# latdr32.net
KiCad netlist of a schematic drawn in EAGLE
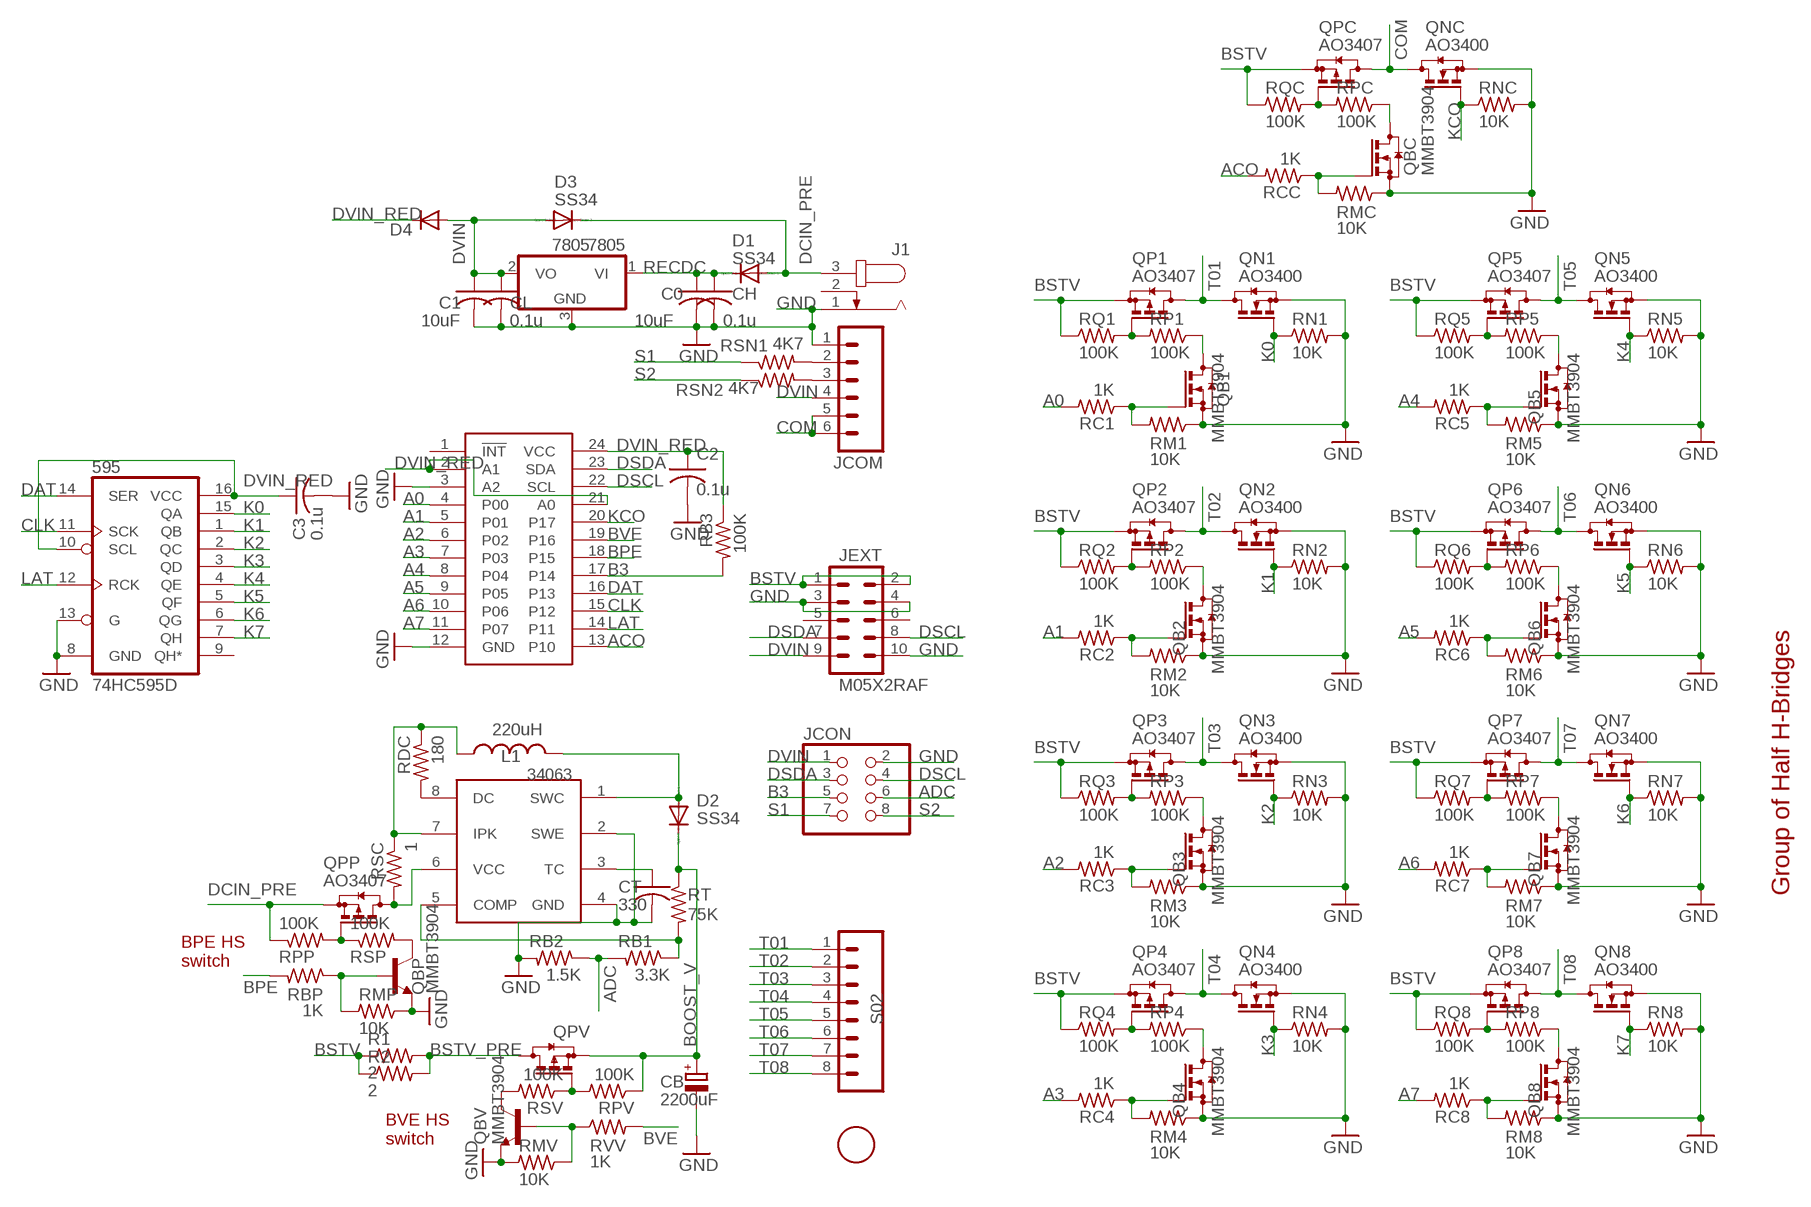
[diagram p0: schematic, sheet 1]

(export (version "E")
  (design (tool "Eeschema 10.0.6"))
  (components
    (comp (ref "1F")
      (value "FIDUCIAL")
      (footprint "eagle-import:FIDUCIAL_1MM")
      (libsource (lib "eagle-import") (part "FIDUCIAL"))
    )
    (comp (ref "595")
      (value "74HC595D")
      (footprint "eagle-import:SO16")
      (libsource (lib "eagle-import") (part "74595DLS"))
    )
    (comp (ref "7805")
      (value "7805")
      (footprint "eagle-import:TO252")
      (libsource (lib "eagle-import") (part "78DT05"))
    )
    (comp (ref "34063")
      (value "MC34063")
      (footprint "eagle-import:SO08")
      (libsource (lib "eagle-import") (part "MC33063/MC34063D"))
    )
    (comp (ref "C0")
      (value "10uF")
      (footprint "eagle-import:C0805K")
      (libsource (lib "eagle-import") (part "C-USC0805K"))
    )
    (comp (ref "C1")
      (value "10uF")
      (footprint "eagle-import:C0805K")
      (libsource (lib "eagle-import") (part "C-USC0805K"))
    )
    (comp (ref "C2")
      (value "0.1u")
      (footprint "eagle-import:C0603")
      (libsource (lib "eagle-import") (part "C-USC0603"))
    )
    (comp (ref "C3")
      (value "0.1u")
      (footprint "eagle-import:C0603")
      (libsource (lib "eagle-import") (part "C-USC0603"))
    )
    (comp (ref "CB")
      (value "2200uF")
      (footprint "eagle-import:E7,5-16")
      (libsource (lib "eagle-import") (part "CPOL-EUE7.5-16"))
    )
    (comp (ref "CH")
      (value "0.1u")
      (footprint "eagle-import:C0603")
      (libsource (lib "eagle-import") (part "C-USC0603"))
    )
    (comp (ref "CL")
      (value "0.1u")
      (footprint "eagle-import:C0603")
      (libsource (lib "eagle-import") (part "C-USC0603"))
    )
    (comp (ref "CT")
      (value "330")
      (footprint "eagle-import:C0603K")
      (libsource (lib "eagle-import") (part "C-USC0603K"))
    )
    (comp (ref "D1")
      (value "SS34")
      (footprint "eagle-import:SMB")
      (libsource (lib "eagle-import") (part "DIODE-SMB"))
    )
    (comp (ref "D2")
      (value "SS34")
      (footprint "eagle-import:SMB")
      (libsource (lib "eagle-import") (part "DIODE-SMB"))
    )
    (comp (ref "D3")
      (value "SS34")
      (footprint "eagle-import:SMB")
      (libsource (lib "eagle-import") (part "DIODE-SMB"))
    )
    (comp (ref "D4")
      (value "DIODESMA")
      (footprint "eagle-import:SMA-DIODE")
      (libsource (lib "eagle-import") (part "DIODESMA"))
    )
    (comp (ref "J1")
      (value "JACK-PLUG0")
      (footprint "eagle-import:SPC4077")
      (libsource (lib "eagle-import") (part "JACK-PLUG0"))
    )
    (comp (ref "JCOM")
      (value "M065MM")
      (footprint "eagle-import:SCREWTERMINAL-5MM-6")
      (libsource (lib "eagle-import") (part "M065MM"))
    )
    (comp (ref "JCON")
      (value "PINHD-2X4")
      (footprint "eagle-import:2X04")
      (libsource (lib "eagle-import") (part "PINHD-2X4"))
    )
    (comp (ref "JEXT")
      (value "M05X2RAF")
      (footprint "eagle-import:2X5-RAF")
      (libsource (lib "eagle-import") (part "M05X2RAF"))
    )
    (comp (ref "L1")
      (value "220uH")
      (footprint "eagle-import:CR54")
      (libsource (lib "eagle-import") (part "INDUCTORCR54"))
    )
    (comp (ref "PCA9555")
      (value "PCA9555")
      (footprint "eagle-import:TSSOP24")
      (libsource (lib "eagle-import") (part "PCF8575TSSOP24"))
    )
    (comp (ref "QB1")
      (value "MMBT3904")
      (footprint "eagle-import:SOT23")
      (libsource (lib "eagle-import") (part "BSS123"))
    )
    (comp (ref "QB2")
      (value "MMBT3904")
      (footprint "eagle-import:SOT23")
      (libsource (lib "eagle-import") (part "BSS123"))
    )
    (comp (ref "QB3")
      (value "MMBT3904")
      (footprint "eagle-import:SOT23")
      (libsource (lib "eagle-import") (part "BSS123"))
    )
    (comp (ref "QB4")
      (value "MMBT3904")
      (footprint "eagle-import:SOT23")
      (libsource (lib "eagle-import") (part "BSS123"))
    )
    (comp (ref "QB5")
      (value "MMBT3904")
      (footprint "eagle-import:SOT23")
      (libsource (lib "eagle-import") (part "BSS123"))
    )
    (comp (ref "QB6")
      (value "MMBT3904")
      (footprint "eagle-import:SOT23")
      (libsource (lib "eagle-import") (part "BSS123"))
    )
    (comp (ref "QB7")
      (value "MMBT3904")
      (footprint "eagle-import:SOT23")
      (libsource (lib "eagle-import") (part "BSS123"))
    )
    (comp (ref "QB8")
      (value "MMBT3904")
      (footprint "eagle-import:SOT23")
      (libsource (lib "eagle-import") (part "BSS123"))
    )
    (comp (ref "QBC")
      (value "MMBT3904")
      (footprint "eagle-import:SOT23")
      (libsource (lib "eagle-import") (part "BSS123"))
    )
    (comp (ref "QBP")
      (value "MMBT3904")
      (footprint "eagle-import:SOT23-3")
      (libsource (lib "eagle-import") (part "TRANSISTOR_NPNSOT23-3"))
    )
    (comp (ref "QBV")
      (value "MMBT3904")
      (footprint "eagle-import:SOT23-3")
      (libsource (lib "eagle-import") (part "TRANSISTOR_NPNSOT23-3"))
    )
    (comp (ref "QN1")
      (value "AO3400")
      (footprint "eagle-import:SOT23")
      (libsource (lib "eagle-import") (part "BSS123"))
    )
    (comp (ref "QN2")
      (value "AO3400")
      (footprint "eagle-import:SOT23")
      (libsource (lib "eagle-import") (part "BSS123"))
    )
    (comp (ref "QN3")
      (value "AO3400")
      (footprint "eagle-import:SOT23")
      (libsource (lib "eagle-import") (part "BSS123"))
    )
    (comp (ref "QN4")
      (value "AO3400")
      (footprint "eagle-import:SOT23")
      (libsource (lib "eagle-import") (part "BSS123"))
    )
    (comp (ref "QN5")
      (value "AO3400")
      (footprint "eagle-import:SOT23")
      (libsource (lib "eagle-import") (part "BSS123"))
    )
    (comp (ref "QN6")
      (value "AO3400")
      (footprint "eagle-import:SOT23")
      (libsource (lib "eagle-import") (part "BSS123"))
    )
    (comp (ref "QN7")
      (value "AO3400")
      (footprint "eagle-import:SOT23")
      (libsource (lib "eagle-import") (part "BSS123"))
    )
    (comp (ref "QN8")
      (value "AO3400")
      (footprint "eagle-import:SOT23")
      (libsource (lib "eagle-import") (part "BSS123"))
    )
    (comp (ref "QNC")
      (value "AO3400")
      (footprint "eagle-import:SOT23")
      (libsource (lib "eagle-import") (part "BSS123"))
    )
    (comp (ref "QP1")
      (value "AO3407")
      (footprint "eagle-import:SOT23")
      (libsource (lib "eagle-import") (part "BSS84"))
    )
    (comp (ref "QP2")
      (value "AO3407")
      (footprint "eagle-import:SOT23")
      (libsource (lib "eagle-import") (part "BSS84"))
    )
    (comp (ref "QP3")
      (value "AO3407")
      (footprint "eagle-import:SOT23")
      (libsource (lib "eagle-import") (part "BSS84"))
    )
    (comp (ref "QP4")
      (value "AO3407")
      (footprint "eagle-import:SOT23")
      (libsource (lib "eagle-import") (part "BSS84"))
    )
    (comp (ref "QP5")
      (value "AO3407")
      (footprint "eagle-import:SOT23")
      (libsource (lib "eagle-import") (part "BSS84"))
    )
    (comp (ref "QP6")
      (value "AO3407")
      (footprint "eagle-import:SOT23")
      (libsource (lib "eagle-import") (part "BSS84"))
    )
    (comp (ref "QP7")
      (value "AO3407")
      (footprint "eagle-import:SOT23")
      (libsource (lib "eagle-import") (part "BSS84"))
    )
    (comp (ref "QP8")
      (value "AO3407")
      (footprint "eagle-import:SOT23")
      (libsource (lib "eagle-import") (part "BSS84"))
    )
    (comp (ref "QPC")
      (value "AO3407")
      (footprint "eagle-import:SOT23")
      (libsource (lib "eagle-import") (part "BSS84"))
    )
    (comp (ref "QPP")
      (value "AO3407")
      (footprint "eagle-import:SOT23")
      (libsource (lib "eagle-import") (part "BSS84"))
    )
    (comp (ref "QPV")
      (value "AO3407")
      (footprint "eagle-import:SOT23")
      (libsource (lib "eagle-import") (part "BSS84"))
    )
    (comp (ref "R1")
      (value "2")
      (footprint "eagle-import:R2512")
      (libsource (lib "eagle-import") (part "R-US_R2512"))
    )
    (comp (ref "R2")
      (value "2")
      (footprint "eagle-import:R2512")
      (libsource (lib "eagle-import") (part "R-US_R2512"))
    )
    (comp (ref "RB1")
      (value "3.3K")
      (footprint "eagle-import:R0603")
      (libsource (lib "eagle-import") (part "adafruitGood_R-US_R0603"))
    )
    (comp (ref "RB2")
      (value "1.5K")
      (footprint "eagle-import:R0603")
      (libsource (lib "eagle-import") (part "adafruitGood_R-US_R0603"))
    )
    (comp (ref "RB3")
      (value "100K")
      (footprint "eagle-import:R0603")
      (libsource (lib "eagle-import") (part "adafruitGood_R-US_R0603"))
    )
    (comp (ref "RBP")
      (value "1K")
      (footprint "eagle-import:R0603")
      (libsource (lib "eagle-import") (part "adafruitGood_R-US_R0603"))
    )
    (comp (ref "RC1")
      (value "1K")
      (footprint "eagle-import:R0603")
      (libsource (lib "eagle-import") (part "adafruitGood_R-US_R0603"))
    )
    (comp (ref "RC2")
      (value "1K")
      (footprint "eagle-import:R0603")
      (libsource (lib "eagle-import") (part "adafruitGood_R-US_R0603"))
    )
    (comp (ref "RC3")
      (value "1K")
      (footprint "eagle-import:R0603")
      (libsource (lib "eagle-import") (part "adafruitGood_R-US_R0603"))
    )
    (comp (ref "RC4")
      (value "1K")
      (footprint "eagle-import:R0603")
      (libsource (lib "eagle-import") (part "adafruitGood_R-US_R0603"))
    )
    (comp (ref "RC5")
      (value "1K")
      (footprint "eagle-import:R0603")
      (libsource (lib "eagle-import") (part "adafruitGood_R-US_R0603"))
    )
    (comp (ref "RC6")
      (value "1K")
      (footprint "eagle-import:R0603")
      (libsource (lib "eagle-import") (part "adafruitGood_R-US_R0603"))
    )
    (comp (ref "RC7")
      (value "1K")
      (footprint "eagle-import:R0603")
      (libsource (lib "eagle-import") (part "adafruitGood_R-US_R0603"))
    )
    (comp (ref "RC8")
      (value "1K")
      (footprint "eagle-import:R0603")
      (libsource (lib "eagle-import") (part "adafruitGood_R-US_R0603"))
    )
    (comp (ref "RCC")
      (value "1K")
      (footprint "eagle-import:R0603")
      (libsource (lib "eagle-import") (part "adafruitGood_R-US_R0603"))
    )
    (comp (ref "RDC")
      (value "180")
      (footprint "eagle-import:R0603")
      (libsource (lib "eagle-import") (part "adafruitGood_R-US_R0603"))
    )
    (comp (ref "RM1")
      (value "10K")
      (footprint "eagle-import:R0603")
      (libsource (lib "eagle-import") (part "adafruitGood_R-US_R0603"))
    )
    (comp (ref "RM2")
      (value "10K")
      (footprint "eagle-import:R0603")
      (libsource (lib "eagle-import") (part "adafruitGood_R-US_R0603"))
    )
    (comp (ref "RM3")
      (value "10K")
      (footprint "eagle-import:R0603")
      (libsource (lib "eagle-import") (part "adafruitGood_R-US_R0603"))
    )
    (comp (ref "RM4")
      (value "10K")
      (footprint "eagle-import:R0603")
      (libsource (lib "eagle-import") (part "adafruitGood_R-US_R0603"))
    )
    (comp (ref "RM5")
      (value "10K")
      (footprint "eagle-import:R0603")
      (libsource (lib "eagle-import") (part "adafruitGood_R-US_R0603"))
    )
    (comp (ref "RM6")
      (value "10K")
      (footprint "eagle-import:R0603")
      (libsource (lib "eagle-import") (part "adafruitGood_R-US_R0603"))
    )
    (comp (ref "RM7")
      (value "10K")
      (footprint "eagle-import:R0603")
      (libsource (lib "eagle-import") (part "adafruitGood_R-US_R0603"))
    )
    (comp (ref "RM8")
      (value "10K")
      (footprint "eagle-import:R0603")
      (libsource (lib "eagle-import") (part "adafruitGood_R-US_R0603"))
    )
    (comp (ref "RMC")
      (value "10K")
      (footprint "eagle-import:R0603")
      (libsource (lib "eagle-import") (part "adafruitGood_R-US_R0603"))
    )
    (comp (ref "RMP")
      (value "10K")
      (footprint "eagle-import:R0603")
      (libsource (lib "eagle-import") (part "adafruitGood_R-US_R0603"))
    )
    (comp (ref "RMV")
      (value "10K")
      (footprint "eagle-import:R0603")
      (libsource (lib "eagle-import") (part "adafruitGood_R-US_R0603"))
    )
    (comp (ref "RN1")
      (value "10K")
      (footprint "eagle-import:R0603")
      (libsource (lib "eagle-import") (part "adafruitGood_R-US_R0603"))
    )
    (comp (ref "RN2")
      (value "10K")
      (footprint "eagle-import:R0603")
      (libsource (lib "eagle-import") (part "adafruitGood_R-US_R0603"))
    )
    (comp (ref "RN3")
      (value "10K")
      (footprint "eagle-import:R0603")
      (libsource (lib "eagle-import") (part "adafruitGood_R-US_R0603"))
    )
    (comp (ref "RN4")
      (value "10K")
      (footprint "eagle-import:R0603")
      (libsource (lib "eagle-import") (part "adafruitGood_R-US_R0603"))
    )
    (comp (ref "RN5")
      (value "10K")
      (footprint "eagle-import:R0603")
      (libsource (lib "eagle-import") (part "adafruitGood_R-US_R0603"))
    )
    (comp (ref "RN6")
      (value "10K")
      (footprint "eagle-import:R0603")
      (libsource (lib "eagle-import") (part "adafruitGood_R-US_R0603"))
    )
    (comp (ref "RN7")
      (value "10K")
      (footprint "eagle-import:R0603")
      (libsource (lib "eagle-import") (part "adafruitGood_R-US_R0603"))
    )
    (comp (ref "RN8")
      (value "10K")
      (footprint "eagle-import:R0603")
      (libsource (lib "eagle-import") (part "adafruitGood_R-US_R0603"))
    )
    (comp (ref "RNC")
      (value "10K")
      (footprint "eagle-import:R0603")
      (libsource (lib "eagle-import") (part "adafruitGood_R-US_R0603"))
    )
    (comp (ref "RP1")
      (value "100K")
      (footprint "eagle-import:R0603")
      (libsource (lib "eagle-import") (part "adafruitGood_R-US_R0603"))
    )
    (comp (ref "RP2")
      (value "100K")
      (footprint "eagle-import:R0603")
      (libsource (lib "eagle-import") (part "adafruitGood_R-US_R0603"))
    )
    (comp (ref "RP3")
      (value "100K")
      (footprint "eagle-import:R0603")
      (libsource (lib "eagle-import") (part "adafruitGood_R-US_R0603"))
    )
    (comp (ref "RP4")
      (value "100K")
      (footprint "eagle-import:R0603")
      (libsource (lib "eagle-import") (part "adafruitGood_R-US_R0603"))
    )
    (comp (ref "RP5")
      (value "100K")
      (footprint "eagle-import:R0603")
      (libsource (lib "eagle-import") (part "adafruitGood_R-US_R0603"))
    )
    (comp (ref "RP6")
      (value "100K")
      (footprint "eagle-import:R0603")
      (libsource (lib "eagle-import") (part "adafruitGood_R-US_R0603"))
    )
    (comp (ref "RP7")
      (value "100K")
      (footprint "eagle-import:R0603")
      (libsource (lib "eagle-import") (part "adafruitGood_R-US_R0603"))
    )
    (comp (ref "RP8")
      (value "100K")
      (footprint "eagle-import:R0603")
      (libsource (lib "eagle-import") (part "adafruitGood_R-US_R0603"))
    )
    (comp (ref "RPC")
      (value "100K")
      (footprint "eagle-import:R0603")
      (libsource (lib "eagle-import") (part "adafruitGood_R-US_R0603"))
    )
    (comp (ref "RPP")
      (value "100K")
      (footprint "eagle-import:R0603")
      (libsource (lib "eagle-import") (part "adafruitGood_R-US_R0603"))
    )
    (comp (ref "RPV")
      (value "100K")
      (footprint "eagle-import:R0603")
      (libsource (lib "eagle-import") (part "adafruitGood_R-US_R0603"))
    )
    (comp (ref "RQ1")
      (value "100K")
      (footprint "eagle-import:R0603")
      (libsource (lib "eagle-import") (part "adafruitGood_R-US_R0603"))
    )
    (comp (ref "RQ2")
      (value "100K")
      (footprint "eagle-import:R0603")
      (libsource (lib "eagle-import") (part "adafruitGood_R-US_R0603"))
    )
    (comp (ref "RQ3")
      (value "100K")
      (footprint "eagle-import:R0603")
      (libsource (lib "eagle-import") (part "adafruitGood_R-US_R0603"))
    )
    (comp (ref "RQ4")
      (value "100K")
      (footprint "eagle-import:R0603")
      (libsource (lib "eagle-import") (part "adafruitGood_R-US_R0603"))
    )
    (comp (ref "RQ5")
      (value "100K")
      (footprint "eagle-import:R0603")
      (libsource (lib "eagle-import") (part "adafruitGood_R-US_R0603"))
    )
    (comp (ref "RQ6")
      (value "100K")
      (footprint "eagle-import:R0603")
      (libsource (lib "eagle-import") (part "adafruitGood_R-US_R0603"))
    )
    (comp (ref "RQ7")
      (value "100K")
      (footprint "eagle-import:R0603")
      (libsource (lib "eagle-import") (part "adafruitGood_R-US_R0603"))
    )
    (comp (ref "RQ8")
      (value "100K")
      (footprint "eagle-import:R0603")
      (libsource (lib "eagle-import") (part "adafruitGood_R-US_R0603"))
    )
    (comp (ref "RQC")
      (value "100K")
      (footprint "eagle-import:R0603")
      (libsource (lib "eagle-import") (part "adafruitGood_R-US_R0603"))
    )
    (comp (ref "RSC")
      (value "1")
      (footprint "eagle-import:R0603")
      (libsource (lib "eagle-import") (part "adafruitGood_R-US_R0603"))
    )
    (comp (ref "RSN1")
      (value "4K7")
      (footprint "eagle-import:R0603")
      (libsource (lib "eagle-import") (part "R-US_R0603"))
    )
    (comp (ref "RSN2")
      (value "4K7")
      (footprint "eagle-import:R0603")
      (libsource (lib "eagle-import") (part "R-US_R0603"))
    )
    (comp (ref "RSP")
      (value "100K")
      (footprint "eagle-import:R0603")
      (libsource (lib "eagle-import") (part "adafruitGood_R-US_R0603"))
    )
    (comp (ref "RSV")
      (value "100K")
      (footprint "eagle-import:R0603")
      (libsource (lib "eagle-import") (part "adafruitGood_R-US_R0603"))
    )
    (comp (ref "RT")
      (value "75K")
      (footprint "eagle-import:R0603")
      (libsource (lib "eagle-import") (part "adafruitGood_R-US_R0603"))
    )
    (comp (ref "RVV")
      (value "1K")
      (footprint "eagle-import:R0603")
      (libsource (lib "eagle-import") (part "adafruitGood_R-US_R0603"))
    )
    (comp (ref "S02")
      (value "M085MM-8")
      (footprint "eagle-import:SCREWTERMINAL-5MM-8")
      (libsource (lib "eagle-import") (part "M085MM-8"))
    )
  )
  (nets
    (net (code "1") (name "/A0") (class "Default")
      (node (ref "PCA9555") (pin "4") (pinfunction "P00_4") (pintype "bidirectional"))
      (node (ref "RC1") (pin "2") (pinfunction "2_2") (pintype "passive"))
    )
    (net (code "2") (name "/A1") (class "Default")
      (node (ref "PCA9555") (pin "5") (pinfunction "P01_5") (pintype "bidirectional"))
      (node (ref "RC2") (pin "2") (pinfunction "2_2") (pintype "passive"))
    )
    (net (code "3") (name "/A2") (class "Default")
      (node (ref "PCA9555") (pin "6") (pinfunction "P02_6") (pintype "bidirectional"))
      (node (ref "RC3") (pin "2") (pinfunction "2_2") (pintype "passive"))
    )
    (net (code "4") (name "/A3") (class "Default")
      (node (ref "PCA9555") (pin "7") (pinfunction "P03_7") (pintype "bidirectional"))
      (node (ref "RC4") (pin "2") (pinfunction "2_2") (pintype "passive"))
    )
    (net (code "5") (name "/A4") (class "Default")
      (node (ref "PCA9555") (pin "8") (pinfunction "P04_8") (pintype "bidirectional"))
      (node (ref "RC5") (pin "2") (pinfunction "2_2") (pintype "passive"))
    )
    (net (code "6") (name "/A5") (class "Default")
      (node (ref "PCA9555") (pin "9") (pinfunction "P05_9") (pintype "bidirectional"))
      (node (ref "RC6") (pin "2") (pinfunction "2_2") (pintype "passive"))
    )
    (net (code "7") (name "/A6") (class "Default")
      (node (ref "PCA9555") (pin "10") (pinfunction "P06_10") (pintype "bidirectional"))
      (node (ref "RC7") (pin "2") (pinfunction "2_2") (pintype "passive"))
    )
    (net (code "8") (name "/A7") (class "Default")
      (node (ref "PCA9555") (pin "11") (pinfunction "P07_11") (pintype "bidirectional"))
      (node (ref "RC8") (pin "2") (pinfunction "2_2") (pintype "passive"))
    )
    (net (code "9") (name "/ACO") (class "Default")
      (node (ref "PCA9555") (pin "13") (pinfunction "P10_13") (pintype "bidirectional"))
      (node (ref "RCC") (pin "2") (pinfunction "2_2") (pintype "passive"))
    )
    (net (code "10") (name "/ADC") (class "Default")
      (node (ref "JCON") (pin "6") (pinfunction "6_6") (pintype "passive"))
      (node (ref "RB1") (pin "2") (pinfunction "2_2") (pintype "passive"))
      (node (ref "RB2") (pin "1") (pinfunction "1_1") (pintype "passive"))
    )
    (net (code "11") (name "/B3") (class "Default")
      (node (ref "JCON") (pin "5") (pinfunction "5_5") (pintype "passive"))
      (node (ref "PCA9555") (pin "17") (pinfunction "P14_17") (pintype "bidirectional"))
      (node (ref "RB3") (pin "2") (pinfunction "2_2") (pintype "passive"))
    )
    (net (code "12") (name "/BOOST_V") (class "Default")
      (node (ref "CB") (pin "+") (pinfunction "+_+") (pintype "passive"))
      (node (ref "D2") (pin "C") (pinfunction "C_C") (pintype "passive"))
      (node (ref "QPV") (pin "2") (pinfunction "S_2") (pintype "passive"))
      (node (ref "RPV") (pin "1") (pinfunction "1_1") (pintype "passive"))
      (node (ref "RT") (pin "1") (pinfunction "1_1") (pintype "passive"))
    )
    (net (code "13") (name "/BPE") (class "Default")
      (node (ref "PCA9555") (pin "18") (pinfunction "P15_18") (pintype "bidirectional"))
      (node (ref "RBP") (pin "2") (pinfunction "2_2") (pintype "passive"))
    )
    (net (code "14") (name "/BSTV") (class "Default")
      (node (ref "JEXT") (pin "1") (pinfunction "1_1") (pintype "passive"))
      (node (ref "JEXT") (pin "2") (pinfunction "2_2") (pintype "passive"))
      (node (ref "QP1") (pin "2") (pinfunction "S_2") (pintype "passive"))
      (node (ref "QP2") (pin "2") (pinfunction "S_2") (pintype "passive"))
      (node (ref "QP3") (pin "2") (pinfunction "S_2") (pintype "passive"))
      (node (ref "QP4") (pin "2") (pinfunction "S_2") (pintype "passive"))
      (node (ref "QP5") (pin "2") (pinfunction "S_2") (pintype "passive"))
      (node (ref "QP6") (pin "2") (pinfunction "S_2") (pintype "passive"))
      (node (ref "QP7") (pin "2") (pinfunction "S_2") (pintype "passive"))
      (node (ref "QP8") (pin "2") (pinfunction "S_2") (pintype "passive"))
      (node (ref "QPC") (pin "2") (pinfunction "S_2") (pintype "passive"))
      (node (ref "R1") (pin "1") (pinfunction "1_1") (pintype "passive"))
      (node (ref "R2") (pin "1") (pinfunction "1_1") (pintype "passive"))
      (node (ref "RQ1") (pin "1") (pinfunction "1_1") (pintype "passive"))
      (node (ref "RQ2") (pin "1") (pinfunction "1_1") (pintype "passive"))
      (node (ref "RQ3") (pin "1") (pinfunction "1_1") (pintype "passive"))
      (node (ref "RQ4") (pin "1") (pinfunction "1_1") (pintype "passive"))
      (node (ref "RQ5") (pin "1") (pinfunction "1_1") (pintype "passive"))
      (node (ref "RQ6") (pin "1") (pinfunction "1_1") (pintype "passive"))
      (node (ref "RQ7") (pin "1") (pinfunction "1_1") (pintype "passive"))
      (node (ref "RQ8") (pin "1") (pinfunction "1_1") (pintype "passive"))
      (node (ref "RQC") (pin "1") (pinfunction "1_1") (pintype "passive"))
    )
    (net (code "15") (name "/BSTV_PRE") (class "Default")
      (node (ref "QPV") (pin "3") (pinfunction "D_3") (pintype "passive"))
      (node (ref "R1") (pin "2") (pinfunction "2_2") (pintype "passive"))
      (node (ref "R2") (pin "2") (pinfunction "2_2") (pintype "passive"))
    )
    (net (code "16") (name "/BVE") (class "Default")
      (node (ref "PCA9555") (pin "19") (pinfunction "P16_19") (pintype "bidirectional"))
      (node (ref "RVV") (pin "2") (pinfunction "2_2") (pintype "passive"))
    )
    (net (code "17") (name "/CLK") (class "Default")
      (node (ref "595") (pin "11") (pinfunction "SCK_11") (pintype "input"))
      (node (ref "PCA9555") (pin "15") (pinfunction "P12_15") (pintype "bidirectional"))
    )
    (net (code "18") (name "/COM") (class "Default")
      (node (ref "JCOM") (pin "5") (pinfunction "5_5") (pintype "passive"))
      (node (ref "JCOM") (pin "6") (pinfunction "6_6") (pintype "passive"))
      (node (ref "QNC") (pin "3") (pinfunction "D_3") (pintype "passive"))
      (node (ref "QPC") (pin "3") (pinfunction "D_3") (pintype "passive"))
    )
    (net (code "19") (name "/DAT") (class "Default")
      (node (ref "595") (pin "14") (pinfunction "SER_14") (pintype "input"))
      (node (ref "PCA9555") (pin "16") (pinfunction "P13_16") (pintype "bidirectional"))
    )
    (net (code "20") (name "/DCIN_PRE") (class "Default")
      (node (ref "D1") (pin "A") (pinfunction "A_A") (pintype "passive"))
      (node (ref "D3") (pin "C") (pinfunction "C_C") (pintype "passive"))
      (node (ref "J1") (pin "3") (pinfunction "3_3") (pintype "passive"))
      (node (ref "QPP") (pin "2") (pinfunction "S_2") (pintype "passive"))
      (node (ref "RPP") (pin "1") (pinfunction "1_1") (pintype "passive"))
    )
    (net (code "21") (name "/DSCL") (class "Default")
      (node (ref "JCON") (pin "4") (pinfunction "4_4") (pintype "passive"))
      (node (ref "JEXT") (pin "8") (pinfunction "8_8") (pintype "passive"))
      (node (ref "PCA9555") (pin "22") (pinfunction "SCL_22") (pintype "bidirectional"))
    )
    (net (code "22") (name "/DSDA") (class "Default")
      (node (ref "JCON") (pin "3") (pinfunction "3_3") (pintype "passive"))
      (node (ref "JEXT") (pin "7") (pinfunction "7_7") (pintype "passive"))
      (node (ref "PCA9555") (pin "23") (pinfunction "SDA_23") (pintype "bidirectional"))
    )
    (net (code "23") (name "/DVIN") (class "Default")
      (node (ref "7805") (pin "2") (pinfunction "VO_2") (pintype "passive"))
      (node (ref "C1") (pin "1") (pinfunction "1_1") (pintype "passive"))
      (node (ref "CL") (pin "1") (pinfunction "1_1") (pintype "passive"))
      (node (ref "D3") (pin "A") (pinfunction "A_A") (pintype "passive"))
      (node (ref "D4") (pin "A") (pinfunction "A_A") (pintype "passive"))
      (node (ref "JCOM") (pin "4") (pinfunction "4_4") (pintype "passive"))
      (node (ref "JCON") (pin "1") (pinfunction "1_1") (pintype "passive"))
      (node (ref "JEXT") (pin "9") (pinfunction "9_9") (pintype "passive"))
    )
    (net (code "24") (name "/DVIN_RED") (class "Default")
      (node (ref "595") (pin "10") (pinfunction "SCL_10") (pintype "input"))
      (node (ref "595") (pin "16") (pinfunction "VCC_16") (pintype "power_in"))
      (node (ref "C2") (pin "1") (pinfunction "1_1") (pintype "passive"))
      (node (ref "C3") (pin "1") (pinfunction "1_1") (pintype "passive"))
      (node (ref "D4") (pin "C") (pinfunction "C_C") (pintype "passive"))
      (node (ref "PCA9555") (pin "2") (pinfunction "A1_2") (pintype "bidirectional"))
      (node (ref "PCA9555") (pin "21") (pinfunction "A0_21") (pintype "bidirectional"))
      (node (ref "PCA9555") (pin "24") (pinfunction "VCC_24") (pintype "power_in"))
      (node (ref "RB3") (pin "1") (pinfunction "1_1") (pintype "passive"))
    )
    (net (code "25") (name "/K0") (class "Default")
      (node (ref "595") (pin "15") (pinfunction "QA_15") (pintype "tri_state"))
      (node (ref "QN1") (pin "1") (pinfunction "G_1") (pintype "passive"))
      (node (ref "RN1") (pin "1") (pinfunction "1_1") (pintype "passive"))
    )
    (net (code "26") (name "/K1") (class "Default")
      (node (ref "595") (pin "1") (pinfunction "QB_1") (pintype "tri_state"))
      (node (ref "QN2") (pin "1") (pinfunction "G_1") (pintype "passive"))
      (node (ref "RN2") (pin "1") (pinfunction "1_1") (pintype "passive"))
    )
    (net (code "27") (name "/K2") (class "Default")
      (node (ref "595") (pin "2") (pinfunction "QC_2") (pintype "tri_state"))
      (node (ref "QN3") (pin "1") (pinfunction "G_1") (pintype "passive"))
      (node (ref "RN3") (pin "1") (pinfunction "1_1") (pintype "passive"))
    )
    (net (code "28") (name "/K3") (class "Default")
      (node (ref "595") (pin "3") (pinfunction "QD_3") (pintype "tri_state"))
      (node (ref "QN4") (pin "1") (pinfunction "G_1") (pintype "passive"))
      (node (ref "RN4") (pin "1") (pinfunction "1_1") (pintype "passive"))
    )
    (net (code "29") (name "/K4") (class "Default")
      (node (ref "595") (pin "4") (pinfunction "QE_4") (pintype "tri_state"))
      (node (ref "QN5") (pin "1") (pinfunction "G_1") (pintype "passive"))
      (node (ref "RN5") (pin "1") (pinfunction "1_1") (pintype "passive"))
    )
    (net (code "30") (name "/K5") (class "Default")
      (node (ref "595") (pin "5") (pinfunction "QF_5") (pintype "tri_state"))
      (node (ref "QN6") (pin "1") (pinfunction "G_1") (pintype "passive"))
      (node (ref "RN6") (pin "1") (pinfunction "1_1") (pintype "passive"))
    )
    (net (code "31") (name "/K6") (class "Default")
      (node (ref "595") (pin "6") (pinfunction "QG_6") (pintype "tri_state"))
      (node (ref "QN7") (pin "1") (pinfunction "G_1") (pintype "passive"))
      (node (ref "RN7") (pin "1") (pinfunction "1_1") (pintype "passive"))
    )
    (net (code "32") (name "/K7") (class "Default")
      (node (ref "595") (pin "7") (pinfunction "QH_7") (pintype "tri_state"))
      (node (ref "QN8") (pin "1") (pinfunction "G_1") (pintype "passive"))
      (node (ref "RN8") (pin "1") (pinfunction "1_1") (pintype "passive"))
    )
    (net (code "33") (name "/KCO") (class "Default")
      (node (ref "PCA9555") (pin "20") (pinfunction "P17_20") (pintype "bidirectional"))
      (node (ref "QNC") (pin "1") (pinfunction "G_1") (pintype "passive"))
      (node (ref "RNC") (pin "1") (pinfunction "1_1") (pintype "passive"))
    )
    (net (code "34") (name "/LAT") (class "Default")
      (node (ref "595") (pin "12") (pinfunction "RCK_12") (pintype "input"))
      (node (ref "PCA9555") (pin "14") (pinfunction "P11_14") (pintype "bidirectional"))
    )
    (net (code "35") (name "/RECDC") (class "Default")
      (node (ref "7805") (pin "1") (pinfunction "VI_1") (pintype "input"))
      (node (ref "C0") (pin "1") (pinfunction "1_1") (pintype "passive"))
      (node (ref "CH") (pin "1") (pinfunction "1_1") (pintype "passive"))
      (node (ref "D1") (pin "C") (pinfunction "C_C") (pintype "passive"))
    )
    (net (code "36") (name "/S1") (class "Default")
      (node (ref "JCON") (pin "7") (pinfunction "7_7") (pintype "passive"))
      (node (ref "RSN1") (pin "1") (pinfunction "1_1") (pintype "passive"))
    )
    (net (code "37") (name "/S2") (class "Default")
      (node (ref "JCON") (pin "8") (pinfunction "8_8") (pintype "passive"))
      (node (ref "RSN2") (pin "1") (pinfunction "1_1") (pintype "passive"))
    )
    (net (code "38") (name "/T01") (class "Default")
      (node (ref "QN1") (pin "3") (pinfunction "D_3") (pintype "passive"))
      (node (ref "QP1") (pin "3") (pinfunction "D_3") (pintype "passive"))
      (node (ref "S02") (pin "1") (pinfunction "1_1") (pintype "passive"))
    )
    (net (code "39") (name "/T02") (class "Default")
      (node (ref "QN2") (pin "3") (pinfunction "D_3") (pintype "passive"))
      (node (ref "QP2") (pin "3") (pinfunction "D_3") (pintype "passive"))
      (node (ref "S02") (pin "2") (pinfunction "2_2") (pintype "passive"))
    )
    (net (code "40") (name "/T03") (class "Default")
      (node (ref "QN3") (pin "3") (pinfunction "D_3") (pintype "passive"))
      (node (ref "QP3") (pin "3") (pinfunction "D_3") (pintype "passive"))
      (node (ref "S02") (pin "3") (pinfunction "3_3") (pintype "passive"))
    )
    (net (code "41") (name "/T04") (class "Default")
      (node (ref "QN4") (pin "3") (pinfunction "D_3") (pintype "passive"))
      (node (ref "QP4") (pin "3") (pinfunction "D_3") (pintype "passive"))
      (node (ref "S02") (pin "4") (pinfunction "4_4") (pintype "passive"))
    )
    (net (code "42") (name "/T05") (class "Default")
      (node (ref "QN5") (pin "3") (pinfunction "D_3") (pintype "passive"))
      (node (ref "QP5") (pin "3") (pinfunction "D_3") (pintype "passive"))
      (node (ref "S02") (pin "5") (pinfunction "5_5") (pintype "passive"))
    )
    (net (code "43") (name "/T06") (class "Default")
      (node (ref "QN6") (pin "3") (pinfunction "D_3") (pintype "passive"))
      (node (ref "QP6") (pin "3") (pinfunction "D_3") (pintype "passive"))
      (node (ref "S02") (pin "6") (pinfunction "6_6") (pintype "passive"))
    )
    (net (code "44") (name "/T07") (class "Default")
      (node (ref "QN7") (pin "3") (pinfunction "D_3") (pintype "passive"))
      (node (ref "QP7") (pin "3") (pinfunction "D_3") (pintype "passive"))
      (node (ref "S02") (pin "7") (pinfunction "7_7") (pintype "passive"))
    )
    (net (code "45") (name "/T08") (class "Default")
      (node (ref "QN8") (pin "3") (pinfunction "D_3") (pintype "passive"))
      (node (ref "QP8") (pin "3") (pinfunction "D_3") (pintype "passive"))
      (node (ref "S02") (pin "8") (pinfunction "8_8") (pintype "passive"))
    )
    (net (code "46") (name "GND") (class "Default")
      (node (ref "34063") (pin "2") (pinfunction "SWE_2") (pintype "input"))
      (node (ref "34063") (pin "4") (pinfunction "GND_4") (pintype "power_in"))
      (node (ref "595") (pin "13") (pinfunction "G_13") (pintype "input"))
      (node (ref "595") (pin "8") (pinfunction "GND_8") (pintype "power_in"))
      (node (ref "7805") (pin "3") (pinfunction "GND_3") (pintype "passive"))
      (node (ref "C0") (pin "2") (pinfunction "2_2") (pintype "passive"))
      (node (ref "C1") (pin "2") (pinfunction "2_2") (pintype "passive"))
      (node (ref "C2") (pin "2") (pinfunction "2_2") (pintype "passive"))
      (node (ref "C3") (pin "2") (pinfunction "2_2") (pintype "passive"))
      (node (ref "CB") (pin "-") (pinfunction "-_-") (pintype "passive"))
      (node (ref "CH") (pin "2") (pinfunction "2_2") (pintype "passive"))
      (node (ref "CL") (pin "2") (pinfunction "2_2") (pintype "passive"))
      (node (ref "CT") (pin "2") (pinfunction "2_2") (pintype "passive"))
      (node (ref "J1") (pin "1") (pinfunction "1_1") (pintype "passive"))
      (node (ref "JCOM") (pin "1") (pinfunction "1_1") (pintype "passive"))
      (node (ref "JCON") (pin "2") (pinfunction "2_2") (pintype "passive"))
      (node (ref "JEXT") (pin "10") (pinfunction "10_10") (pintype "passive"))
      (node (ref "JEXT") (pin "3") (pinfunction "3_3") (pintype "passive"))
      (node (ref "JEXT") (pin "4") (pinfunction "4_4") (pintype "passive"))
      (node (ref "PCA9555") (pin "12") (pinfunction "GND_12") (pintype "power_in"))
      (node (ref "PCA9555") (pin "3") (pinfunction "A2_3") (pintype "bidirectional"))
      (node (ref "QB1") (pin "2") (pinfunction "S_2") (pintype "passive"))
      (node (ref "QB2") (pin "2") (pinfunction "S_2") (pintype "passive"))
      (node (ref "QB3") (pin "2") (pinfunction "S_2") (pintype "passive"))
      (node (ref "QB4") (pin "2") (pinfunction "S_2") (pintype "passive"))
      (node (ref "QB5") (pin "2") (pinfunction "S_2") (pintype "passive"))
      (node (ref "QB6") (pin "2") (pinfunction "S_2") (pintype "passive"))
      (node (ref "QB7") (pin "2") (pinfunction "S_2") (pintype "passive"))
      (node (ref "QB8") (pin "2") (pinfunction "S_2") (pintype "passive"))
      (node (ref "QBC") (pin "2") (pinfunction "S_2") (pintype "passive"))
      (node (ref "QBP") (pin "2") (pinfunction "E_2") (pintype "passive"))
      (node (ref "QBV") (pin "2") (pinfunction "E_2") (pintype "passive"))
      (node (ref "QN1") (pin "2") (pinfunction "S_2") (pintype "passive"))
      (node (ref "QN2") (pin "2") (pinfunction "S_2") (pintype "passive"))
      (node (ref "QN3") (pin "2") (pinfunction "S_2") (pintype "passive"))
      (node (ref "QN4") (pin "2") (pinfunction "S_2") (pintype "passive"))
      (node (ref "QN5") (pin "2") (pinfunction "S_2") (pintype "passive"))
      (node (ref "QN6") (pin "2") (pinfunction "S_2") (pintype "passive"))
      (node (ref "QN7") (pin "2") (pinfunction "S_2") (pintype "passive"))
      (node (ref "QN8") (pin "2") (pinfunction "S_2") (pintype "passive"))
      (node (ref "QNC") (pin "2") (pinfunction "S_2") (pintype "passive"))
      (node (ref "RB2") (pin "2") (pinfunction "2_2") (pintype "passive"))
      (node (ref "RM1") (pin "1") (pinfunction "1_1") (pintype "passive"))
      (node (ref "RM2") (pin "1") (pinfunction "1_1") (pintype "passive"))
      (node (ref "RM3") (pin "1") (pinfunction "1_1") (pintype "passive"))
      (node (ref "RM4") (pin "1") (pinfunction "1_1") (pintype "passive"))
      (node (ref "RM5") (pin "1") (pinfunction "1_1") (pintype "passive"))
      (node (ref "RM6") (pin "1") (pinfunction "1_1") (pintype "passive"))
      (node (ref "RM7") (pin "1") (pinfunction "1_1") (pintype "passive"))
      (node (ref "RM8") (pin "1") (pinfunction "1_1") (pintype "passive"))
      (node (ref "RMC") (pin "1") (pinfunction "1_1") (pintype "passive"))
      (node (ref "RMP") (pin "1") (pinfunction "1_1") (pintype "passive"))
      (node (ref "RMV") (pin "2") (pinfunction "2_2") (pintype "passive"))
      (node (ref "RN1") (pin "2") (pinfunction "2_2") (pintype "passive"))
      (node (ref "RN2") (pin "2") (pinfunction "2_2") (pintype "passive"))
      (node (ref "RN3") (pin "2") (pinfunction "2_2") (pintype "passive"))
      (node (ref "RN4") (pin "2") (pinfunction "2_2") (pintype "passive"))
      (node (ref "RN5") (pin "2") (pinfunction "2_2") (pintype "passive"))
      (node (ref "RN6") (pin "2") (pinfunction "2_2") (pintype "passive"))
      (node (ref "RN7") (pin "2") (pinfunction "2_2") (pintype "passive"))
      (node (ref "RN8") (pin "2") (pinfunction "2_2") (pintype "passive"))
      (node (ref "RNC") (pin "2") (pinfunction "2_2") (pintype "passive"))
    )
    (net (code "47") (name "Net-(34063-COMP)") (class "Default")
      (node (ref "34063") (pin "5") (pinfunction "COMP_5") (pintype "input"))
      (node (ref "RB1") (pin "1") (pinfunction "1_1") (pintype "passive"))
      (node (ref "RT") (pin "2") (pinfunction "2_2") (pintype "passive"))
    )
    (net (code "48") (name "Net-(34063-DC)") (class "Default")
      (node (ref "34063") (pin "8") (pinfunction "DC_8") (pintype "input"))
      (node (ref "RDC") (pin "2") (pinfunction "2_2") (pintype "passive"))
    )
    (net (code "49") (name "Net-(34063-IPK)") (class "Default")
      (node (ref "34063") (pin "7") (pinfunction "IPK_7") (pintype "bidirectional"))
      (node (ref "L1") (pin "P$1") (pinfunction "1_P$1") (pintype "passive"))
      (node (ref "RDC") (pin "1") (pinfunction "1_1") (pintype "passive"))
      (node (ref "RSC") (pin "1") (pinfunction "1_1") (pintype "passive"))
    )
    (net (code "50") (name "Net-(34063-SWC)") (class "Default")
      (node (ref "34063") (pin "1") (pinfunction "SWC_1") (pintype "input"))
      (node (ref "D2") (pin "A") (pinfunction "A_A") (pintype "passive"))
      (node (ref "L1") (pin "P$2") (pinfunction "2_P$2") (pintype "passive"))
    )
    (net (code "51") (name "Net-(34063-TC)") (class "Default")
      (node (ref "34063") (pin "3") (pinfunction "TC_3") (pintype "input"))
      (node (ref "CT") (pin "1") (pinfunction "1_1") (pintype "passive"))
    )
    (net (code "52") (name "Net-(34063-VCC)") (class "Default")
      (node (ref "34063") (pin "6") (pinfunction "VCC_6") (pintype "power_in"))
      (node (ref "QPP") (pin "3") (pinfunction "D_3") (pintype "passive"))
      (node (ref "RSC") (pin "2") (pinfunction "2_2") (pintype "passive"))
    )
    (net (code "53") (name "Net-(JCOM-Pad2)") (class "Default")
      (node (ref "JCOM") (pin "2") (pinfunction "2_2") (pintype "passive"))
      (node (ref "RSN1") (pin "2") (pinfunction "2_2") (pintype "passive"))
    )
    (net (code "54") (name "Net-(JCOM-Pad3)") (class "Default")
      (node (ref "JCOM") (pin "3") (pinfunction "3_3") (pintype "passive"))
      (node (ref "RSN2") (pin "2") (pinfunction "2_2") (pintype "passive"))
    )
    (net (code "55") (name "Net-(QB1-D)") (class "Default")
      (node (ref "QB1") (pin "3") (pinfunction "D_3") (pintype "passive"))
      (node (ref "RP1") (pin "1") (pinfunction "1_1") (pintype "passive"))
    )
    (net (code "56") (name "Net-(QB1-G)") (class "Default")
      (node (ref "QB1") (pin "1") (pinfunction "G_1") (pintype "passive"))
      (node (ref "RC1") (pin "1") (pinfunction "1_1") (pintype "passive"))
      (node (ref "RM1") (pin "2") (pinfunction "2_2") (pintype "passive"))
    )
    (net (code "57") (name "Net-(QB2-D)") (class "Default")
      (node (ref "QB2") (pin "3") (pinfunction "D_3") (pintype "passive"))
      (node (ref "RP2") (pin "1") (pinfunction "1_1") (pintype "passive"))
    )
    (net (code "58") (name "Net-(QB2-G)") (class "Default")
      (node (ref "QB2") (pin "1") (pinfunction "G_1") (pintype "passive"))
      (node (ref "RC2") (pin "1") (pinfunction "1_1") (pintype "passive"))
      (node (ref "RM2") (pin "2") (pinfunction "2_2") (pintype "passive"))
    )
    (net (code "59") (name "Net-(QB3-D)") (class "Default")
      (node (ref "QB3") (pin "3") (pinfunction "D_3") (pintype "passive"))
      (node (ref "RP3") (pin "1") (pinfunction "1_1") (pintype "passive"))
    )
    (net (code "60") (name "Net-(QB3-G)") (class "Default")
      (node (ref "QB3") (pin "1") (pinfunction "G_1") (pintype "passive"))
      (node (ref "RC3") (pin "1") (pinfunction "1_1") (pintype "passive"))
      (node (ref "RM3") (pin "2") (pinfunction "2_2") (pintype "passive"))
    )
    (net (code "61") (name "Net-(QB4-D)") (class "Default")
      (node (ref "QB4") (pin "3") (pinfunction "D_3") (pintype "passive"))
      (node (ref "RP4") (pin "1") (pinfunction "1_1") (pintype "passive"))
    )
    (net (code "62") (name "Net-(QB4-G)") (class "Default")
      (node (ref "QB4") (pin "1") (pinfunction "G_1") (pintype "passive"))
      (node (ref "RC4") (pin "1") (pinfunction "1_1") (pintype "passive"))
      (node (ref "RM4") (pin "2") (pinfunction "2_2") (pintype "passive"))
    )
    (net (code "63") (name "Net-(QB5-D)") (class "Default")
      (node (ref "QB5") (pin "3") (pinfunction "D_3") (pintype "passive"))
      (node (ref "RP5") (pin "1") (pinfunction "1_1") (pintype "passive"))
    )
    (net (code "64") (name "Net-(QB5-G)") (class "Default")
      (node (ref "QB5") (pin "1") (pinfunction "G_1") (pintype "passive"))
      (node (ref "RC5") (pin "1") (pinfunction "1_1") (pintype "passive"))
      (node (ref "RM5") (pin "2") (pinfunction "2_2") (pintype "passive"))
    )
    (net (code "65") (name "Net-(QB6-D)") (class "Default")
      (node (ref "QB6") (pin "3") (pinfunction "D_3") (pintype "passive"))
      (node (ref "RP6") (pin "1") (pinfunction "1_1") (pintype "passive"))
    )
    (net (code "66") (name "Net-(QB6-G)") (class "Default")
      (node (ref "QB6") (pin "1") (pinfunction "G_1") (pintype "passive"))
      (node (ref "RC6") (pin "1") (pinfunction "1_1") (pintype "passive"))
      (node (ref "RM6") (pin "2") (pinfunction "2_2") (pintype "passive"))
    )
    (net (code "67") (name "Net-(QB7-D)") (class "Default")
      (node (ref "QB7") (pin "3") (pinfunction "D_3") (pintype "passive"))
      (node (ref "RP7") (pin "1") (pinfunction "1_1") (pintype "passive"))
    )
    (net (code "68") (name "Net-(QB7-G)") (class "Default")
      (node (ref "QB7") (pin "1") (pinfunction "G_1") (pintype "passive"))
      (node (ref "RC7") (pin "1") (pinfunction "1_1") (pintype "passive"))
      (node (ref "RM7") (pin "2") (pinfunction "2_2") (pintype "passive"))
    )
    (net (code "69") (name "Net-(QB8-D)") (class "Default")
      (node (ref "QB8") (pin "3") (pinfunction "D_3") (pintype "passive"))
      (node (ref "RP8") (pin "1") (pinfunction "1_1") (pintype "passive"))
    )
    (net (code "70") (name "Net-(QB8-G)") (class "Default")
      (node (ref "QB8") (pin "1") (pinfunction "G_1") (pintype "passive"))
      (node (ref "RC8") (pin "1") (pinfunction "1_1") (pintype "passive"))
      (node (ref "RM8") (pin "2") (pinfunction "2_2") (pintype "passive"))
    )
    (net (code "71") (name "Net-(QBC-D)") (class "Default")
      (node (ref "QBC") (pin "3") (pinfunction "D_3") (pintype "passive"))
      (node (ref "RPC") (pin "1") (pinfunction "1_1") (pintype "passive"))
    )
    (net (code "72") (name "Net-(QBC-G)") (class "Default")
      (node (ref "QBC") (pin "1") (pinfunction "G_1") (pintype "passive"))
      (node (ref "RCC") (pin "1") (pinfunction "1_1") (pintype "passive"))
      (node (ref "RMC") (pin "2") (pinfunction "2_2") (pintype "passive"))
    )
    (net (code "73") (name "Net-(QBP-B)") (class "Default")
      (node (ref "QBP") (pin "1") (pinfunction "B_1") (pintype "passive"))
      (node (ref "RBP") (pin "1") (pinfunction "1_1") (pintype "passive"))
      (node (ref "RMP") (pin "2") (pinfunction "2_2") (pintype "passive"))
    )
    (net (code "74") (name "Net-(QBP-C)") (class "Default")
      (node (ref "QBP") (pin "3") (pinfunction "C_3") (pintype "passive"))
      (node (ref "RSP") (pin "2") (pinfunction "2_2") (pintype "passive"))
    )
    (net (code "75") (name "Net-(QBV-B)") (class "Default")
      (node (ref "QBV") (pin "1") (pinfunction "B_1") (pintype "passive"))
      (node (ref "RMV") (pin "1") (pinfunction "1_1") (pintype "passive"))
      (node (ref "RVV") (pin "1") (pinfunction "1_1") (pintype "passive"))
    )
    (net (code "76") (name "Net-(QBV-C)") (class "Default")
      (node (ref "QBV") (pin "3") (pinfunction "C_3") (pintype "passive"))
      (node (ref "RSV") (pin "2") (pinfunction "2_2") (pintype "passive"))
    )
    (net (code "77") (name "Net-(QP1-G)") (class "Default")
      (node (ref "QP1") (pin "1") (pinfunction "G_1") (pintype "passive"))
      (node (ref "RP1") (pin "2") (pinfunction "2_2") (pintype "passive"))
      (node (ref "RQ1") (pin "2") (pinfunction "2_2") (pintype "passive"))
    )
    (net (code "78") (name "Net-(QP2-G)") (class "Default")
      (node (ref "QP2") (pin "1") (pinfunction "G_1") (pintype "passive"))
      (node (ref "RP2") (pin "2") (pinfunction "2_2") (pintype "passive"))
      (node (ref "RQ2") (pin "2") (pinfunction "2_2") (pintype "passive"))
    )
    (net (code "79") (name "Net-(QP3-G)") (class "Default")
      (node (ref "QP3") (pin "1") (pinfunction "G_1") (pintype "passive"))
      (node (ref "RP3") (pin "2") (pinfunction "2_2") (pintype "passive"))
      (node (ref "RQ3") (pin "2") (pinfunction "2_2") (pintype "passive"))
    )
    (net (code "80") (name "Net-(QP4-G)") (class "Default")
      (node (ref "QP4") (pin "1") (pinfunction "G_1") (pintype "passive"))
      (node (ref "RP4") (pin "2") (pinfunction "2_2") (pintype "passive"))
      (node (ref "RQ4") (pin "2") (pinfunction "2_2") (pintype "passive"))
    )
    (net (code "81") (name "Net-(QP5-G)") (class "Default")
      (node (ref "QP5") (pin "1") (pinfunction "G_1") (pintype "passive"))
      (node (ref "RP5") (pin "2") (pinfunction "2_2") (pintype "passive"))
      (node (ref "RQ5") (pin "2") (pinfunction "2_2") (pintype "passive"))
    )
    (net (code "82") (name "Net-(QP6-G)") (class "Default")
      (node (ref "QP6") (pin "1") (pinfunction "G_1") (pintype "passive"))
      (node (ref "RP6") (pin "2") (pinfunction "2_2") (pintype "passive"))
      (node (ref "RQ6") (pin "2") (pinfunction "2_2") (pintype "passive"))
    )
    (net (code "83") (name "Net-(QP7-G)") (class "Default")
      (node (ref "QP7") (pin "1") (pinfunction "G_1") (pintype "passive"))
      (node (ref "RP7") (pin "2") (pinfunction "2_2") (pintype "passive"))
      (node (ref "RQ7") (pin "2") (pinfunction "2_2") (pintype "passive"))
    )
    (net (code "84") (name "Net-(QP8-G)") (class "Default")
      (node (ref "QP8") (pin "1") (pinfunction "G_1") (pintype "passive"))
      (node (ref "RP8") (pin "2") (pinfunction "2_2") (pintype "passive"))
      (node (ref "RQ8") (pin "2") (pinfunction "2_2") (pintype "passive"))
    )
    (net (code "85") (name "Net-(QPC-G)") (class "Default")
      (node (ref "QPC") (pin "1") (pinfunction "G_1") (pintype "passive"))
      (node (ref "RPC") (pin "2") (pinfunction "2_2") (pintype "passive"))
      (node (ref "RQC") (pin "2") (pinfunction "2_2") (pintype "passive"))
    )
    (net (code "86") (name "Net-(QPP-G)") (class "Default")
      (node (ref "QPP") (pin "1") (pinfunction "G_1") (pintype "passive"))
      (node (ref "RPP") (pin "2") (pinfunction "2_2") (pintype "passive"))
      (node (ref "RSP") (pin "1") (pinfunction "1_1") (pintype "passive"))
    )
    (net (code "87") (name "Net-(QPV-G)") (class "Default")
      (node (ref "QPV") (pin "1") (pinfunction "G_1") (pintype "passive"))
      (node (ref "RPV") (pin "2") (pinfunction "2_2") (pintype "passive"))
      (node (ref "RSV") (pin "1") (pinfunction "1_1") (pintype "passive"))
    )
    (net (code "88") (name "unconnected-(595-QH*-Pad9)") (class "Default")
      (node (ref "595") (pin "9") (pinfunction "QH*_9") (pintype "tri_state"))
    )
    (net (code "89") (name "unconnected-(J1-Pad2)") (class "Default")
      (node (ref "J1") (pin "2") (pinfunction "2_2") (pintype "passive"))
    )
    (net (code "90") (name "unconnected-(JEXT-Pad5)") (class "Default")
      (node (ref "JEXT") (pin "5") (pinfunction "5_5") (pintype "passive"))
    )
    (net (code "91") (name "unconnected-(JEXT-Pad6)") (class "Default")
      (node (ref "JEXT") (pin "6") (pinfunction "6_6") (pintype "passive"))
    )
    (net (code "92") (name "unconnected-(PCA9555-~{INT}-Pad1)") (class "Default")
      (node (ref "PCA9555") (pin "1") (pinfunction "~{INT}_1") (pintype "bidirectional"))
    )
  )
)
